# NODE_2_SCH.net
KiCad netlist of a schematic drawn in Altium Designer
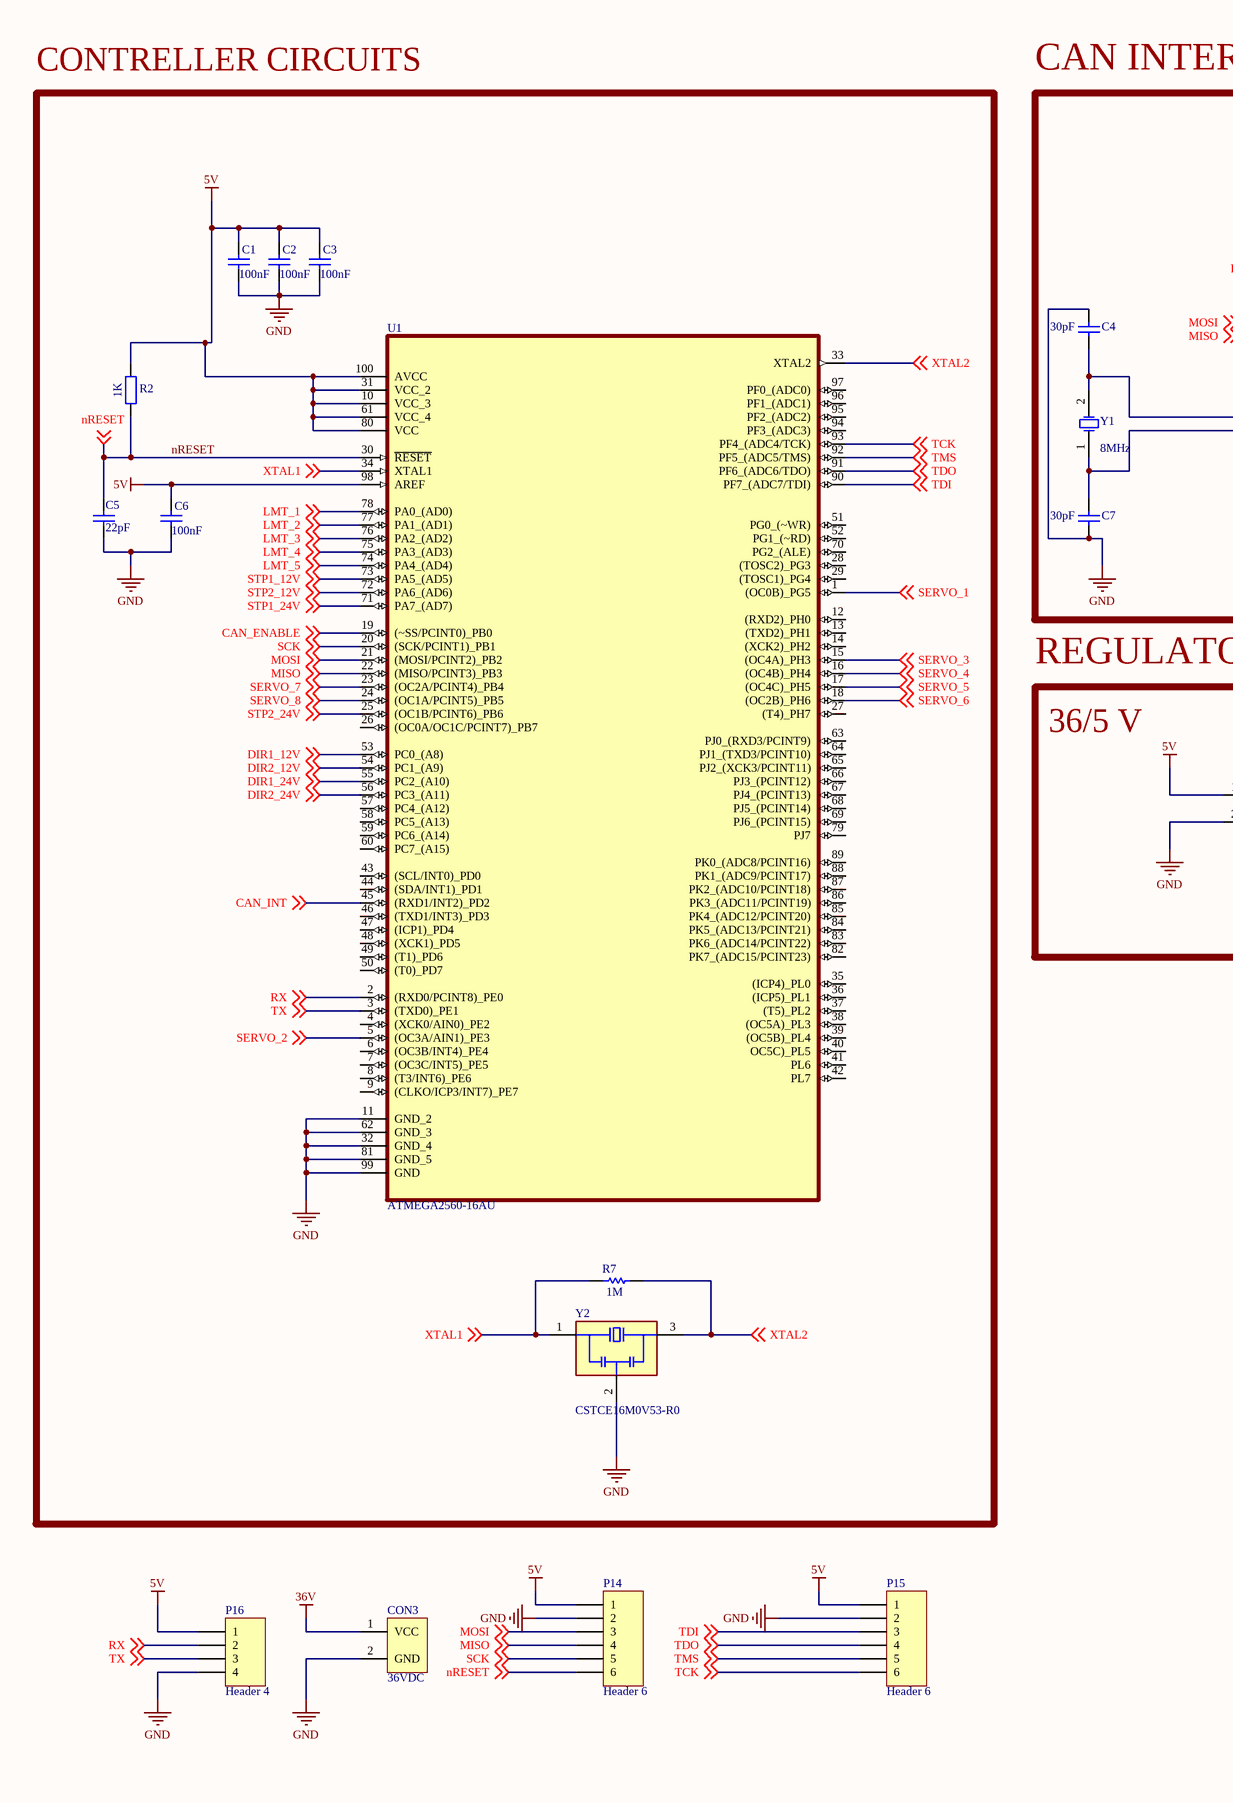
[diagram p0: NODE_2_SCH.SchDoc, left]
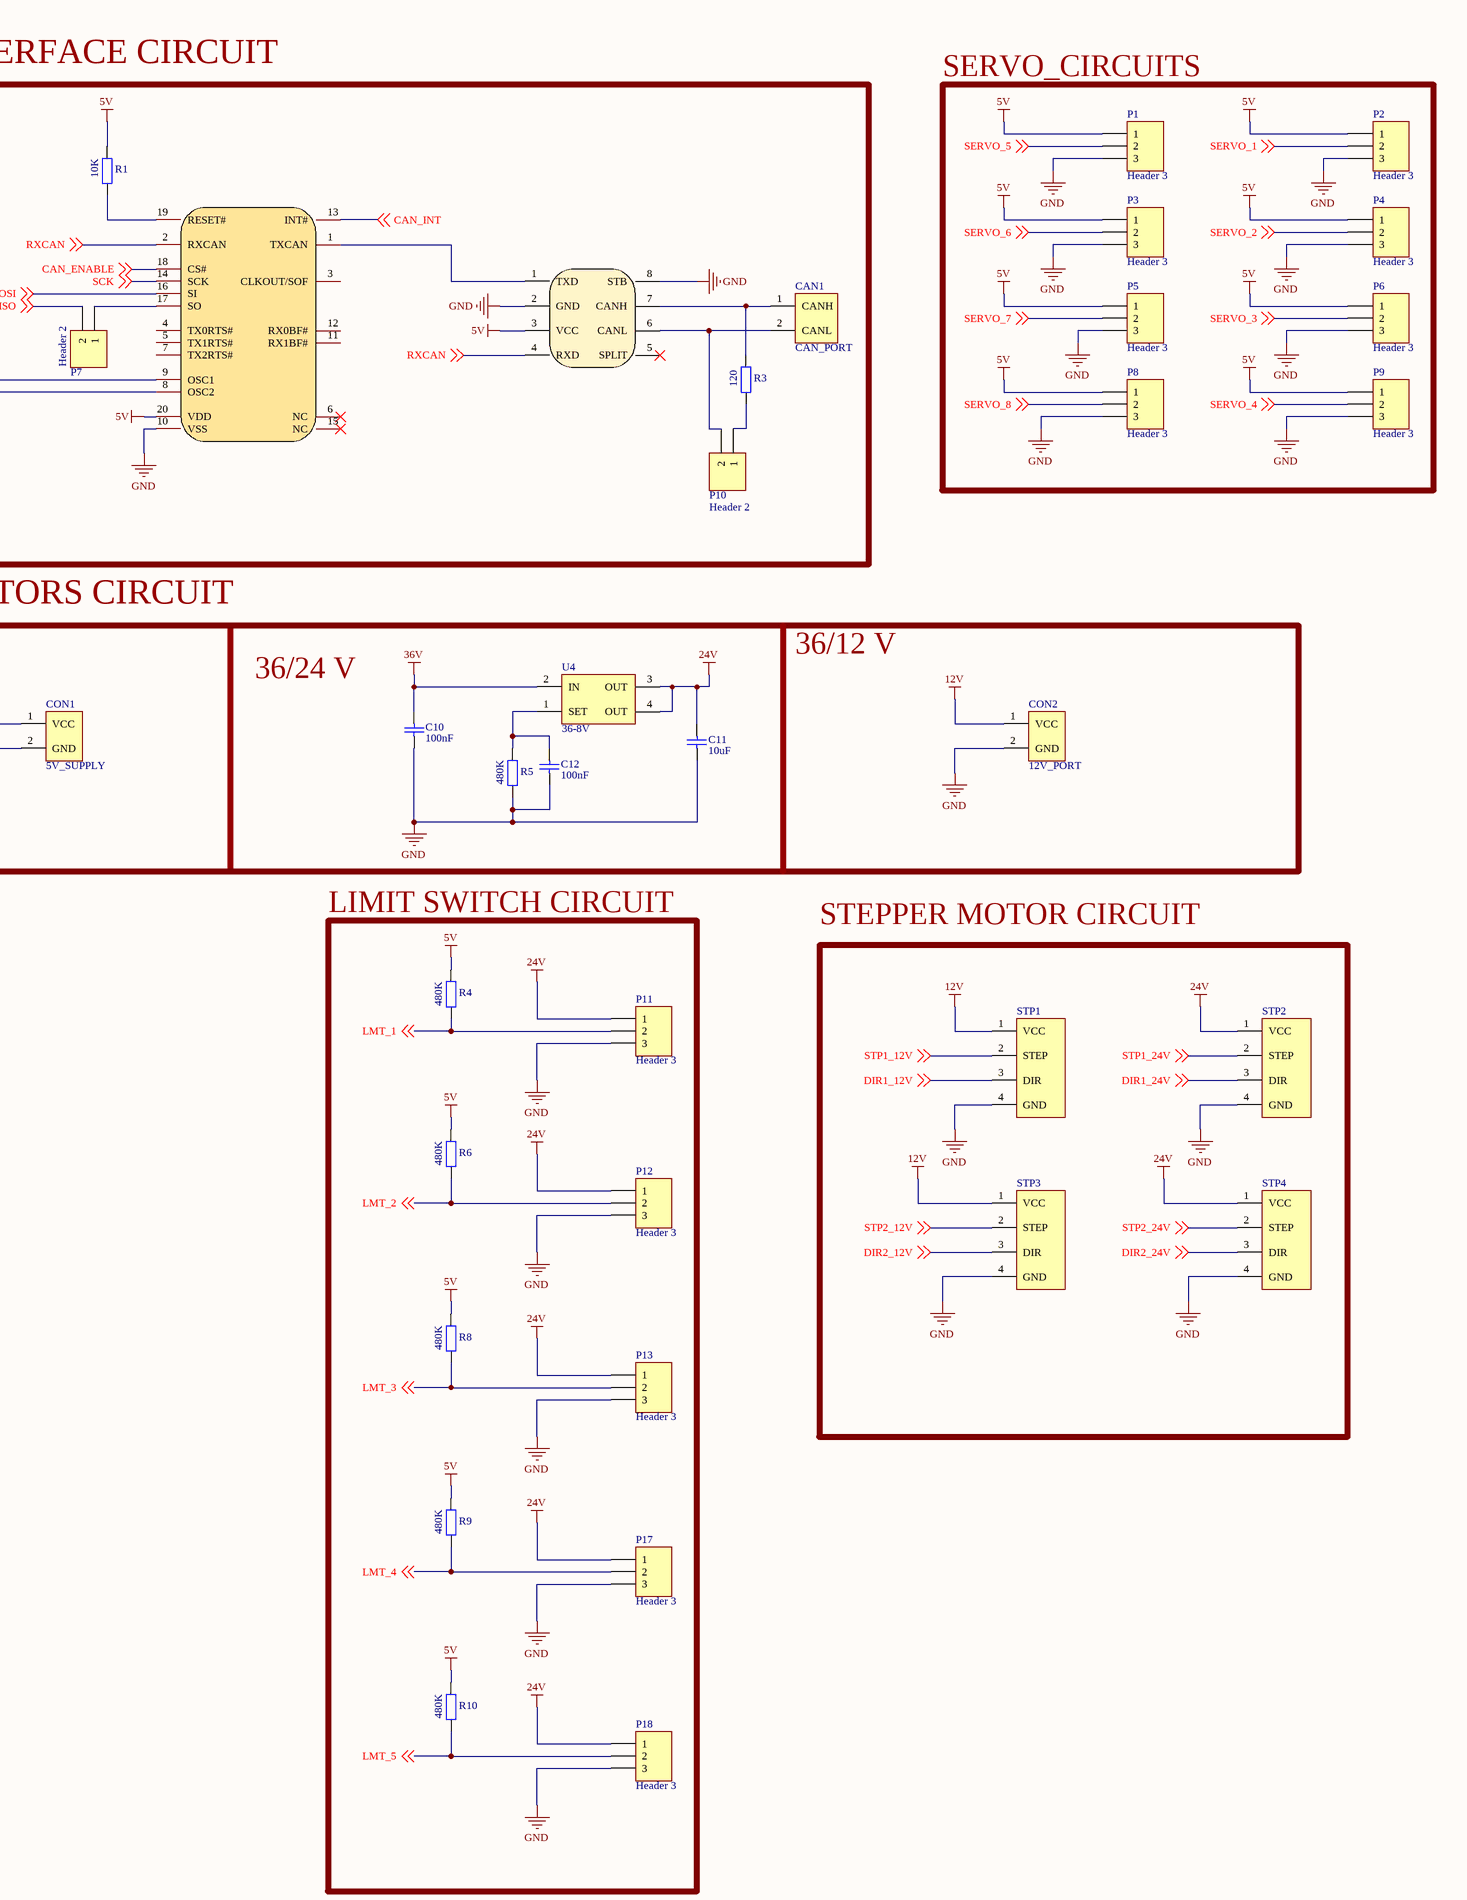
[diagram p1: NODE_2_SCH.SchDoc, right]

(export (version "E")
  (design (tool "Eeschema 10.0.6"))
  (components
    (comp (ref "C1")
      (value "100nF")
      (footprint "CAPC2012X135N")
      (description "Capacitor")
      (fields
        (field (name "PART NUMBER") "TCC0805X7R104M500DT")
        (field (name "Comment") "Cap")
        (field (name "PUBLISHER") "Altium Limited")
      )
      (libsource (lib "Miscellaneous Devices") (part "Cap"))
    )
    (comp (ref "C2")
      (value "100nF")
      (footprint "CAPC2012X135N")
      (description "Capacitor")
      (fields
        (field (name "PART NUMBER") "TCC0805X7R104M500DT")
        (field (name "Comment") "Cap")
        (field (name "PUBLISHER") "Altium Limited")
      )
      (libsource (lib "Miscellaneous Devices") (part "Cap"))
    )
    (comp (ref "C3")
      (value "100nF")
      (footprint "CAPC2012X135N")
      (description "Capacitor")
      (fields
        (field (name "PART NUMBER") "TCC0805X7R104M500DT")
        (field (name "Comment") "Cap")
        (field (name "PUBLISHER") "Altium Limited")
      )
      (libsource (lib "Miscellaneous Devices") (part "Cap"))
    )
    (comp (ref "C4")
      (value "30pF")
      (footprint "CAPC2012X135N")
      (description "Capacitor")
      (fields
        (field (name "PART NUMBER") "TCC0805COG300J500BT")
        (field (name "Comment") "Cap")
        (field (name "PUBLISHER") "Altium Limited")
      )
      (libsource (lib "Miscellaneous Devices") (part "Cap"))
    )
    (comp (ref "C5")
      (value "22pF")
      (footprint "CAPC2012X135N")
      (description "Capacitor")
      (fields
        (field (name "PART NUMBER") "TCC0805COG220J500BT")
        (field (name "Comment") "Cap")
        (field (name "PUBLISHER") "Altium Limited")
      )
      (libsource (lib "Miscellaneous Devices") (part "Cap"))
    )
    (comp (ref "C6")
      (value "100nF")
      (footprint "CAPC2012X135N")
      (description "Capacitor")
      (fields
        (field (name "PART NUMBER") "TCC0805X7R104M500DT")
        (field (name "Comment") "Cap")
        (field (name "PUBLISHER") "Altium Limited")
      )
      (libsource (lib "Miscellaneous Devices") (part "Cap"))
    )
    (comp (ref "C7")
      (value "30pF")
      (footprint "CAPC2012X135N")
      (description "Capacitor")
      (fields
        (field (name "PART NUMBER") "TCC0805COG300J500BT")
        (field (name "Comment") "Cap")
        (field (name "PUBLISHER") "Altium Limited")
      )
      (libsource (lib "Miscellaneous Devices") (part "Cap"))
    )
    (comp (ref "C10")
      (value "100nF")
      (footprint "CAPC2012X135N")
      (description "Capacitor")
      (fields
        (field (name "PART NUMBER") "TCC0805X7R104M500DT")
        (field (name "Comment") "Cap")
        (field (name "PUBLISHER") "Altium Limited")
      )
      (libsource (lib "Miscellaneous Devices") (part "Cap"))
    )
    (comp (ref "C11")
      (value "10uF")
      (footprint "CAPC2012X135N")
      (description "Capacitor")
      (fields
        (field (name "PART NUMBER") "CL21A106KOQNNNE")
        (field (name "Comment") "Cap")
        (field (name "PUBLISHER") "Altium Limited")
      )
      (libsource (lib "Miscellaneous Devices") (part "Cap"))
    )
    (comp (ref "C12")
      (value "100nF")
      (footprint "CAPC2012X135N")
      (description "Capacitor")
      (fields
        (field (name "PART NUMBER") "TCC0805X7R104M500DT")
        (field (name "Comment") "Cap")
        (field (name "PUBLISHER") "Altium Limited")
      )
      (libsource (lib "Miscellaneous Devices") (part "Cap"))
    )
    (comp (ref "CAN1")
      (value "CAN_PORT")
      (footprint "12V_CON")
      (fields (field (name "PART NUMBER") "MX126-5.0-02P-GN01-Cu-S-A"))
      (libsource (lib "IOT_Library") (part "2PIN_CON_1"))
    )
    (comp (ref "CON1")
      (value "5V_SUPPLY")
      (footprint "12V_CON")
      (fields (field (name "PART NUMBER") "MX126-5.0-02P-GN01-Cu-S-A"))
      (libsource (lib "IOT_Library") (part "2PIN_CON"))
    )
    (comp (ref "CON2")
      (value "12V_PORT")
      (footprint "12V_CON")
      (fields (field (name "PART NUMBER") "MX126-5.0-02P-GN01-Cu-S-A"))
      (libsource (lib "IOT_Library") (part "2PIN_CON"))
    )
    (comp (ref "CON3")
      (value "36VDC")
      (footprint "12V_CON")
      (fields (field (name "PART NUMBER") "MX126-5.0-02P-GN01-Cu-S-A"))
      (libsource (lib "IOT_Library") (part "2PIN_CON_2"))
    )
    (comp (ref "P1")
      (value "Header 3")
      (footprint "3PIN_H")
      (description "Header, 3-Pin")
      (fields (field (name "PART NUMBER") "DB125-3.81-3P-BK-S") (field (name "PUBLISHER") "Altium Limited"))
      (libsource (lib "Miscellaneous Connectors") (part "Header 3"))
    )
    (comp (ref "P2")
      (value "Header 3")
      (footprint "3PIN_H")
      (description "Header, 3-Pin")
      (fields (field (name "PART NUMBER") "DB125-3.81-3P-BK-S") (field (name "PUBLISHER") "Altium Limited"))
      (libsource (lib "Miscellaneous Connectors") (part "Header 3"))
    )
    (comp (ref "P3")
      (value "Header 3")
      (footprint "3PIN_H")
      (description "Header, 3-Pin")
      (fields (field (name "PART NUMBER") "DB125-3.81-3P-BK-S") (field (name "PUBLISHER") "Altium Limited"))
      (libsource (lib "Miscellaneous Connectors") (part "Header 3"))
    )
    (comp (ref "P4")
      (value "Header 3")
      (footprint "3PIN_H")
      (description "Header, 3-Pin")
      (fields (field (name "PART NUMBER") "DB125-3.81-3P-BK-S") (field (name "PUBLISHER") "Altium Limited"))
      (libsource (lib "Miscellaneous Connectors") (part "Header 3"))
    )
    (comp (ref "P5")
      (value "Header 3")
      (footprint "3PIN_H")
      (description "Header, 3-Pin")
      (fields (field (name "PART NUMBER") "DB125-3.81-3P-BK-S") (field (name "PUBLISHER") "Altium Limited"))
      (libsource (lib "Miscellaneous Connectors") (part "Header 3"))
    )
    (comp (ref "P6")
      (value "Header 3")
      (footprint "3PIN_H")
      (description "Header, 3-Pin")
      (fields (field (name "PART NUMBER") "DB125-3.81-3P-BK-S") (field (name "PUBLISHER") "Altium Limited"))
      (libsource (lib "Miscellaneous Connectors") (part "Header 3"))
    )
    (comp (ref "P7")
      (value "Header 2")
      (footprint "SAMTEC_TS-102-G-A")
      (description "Header, 2-Pin")
      (fields (field (name "PART NUMBER") "PH-01078") (field (name "PUBLISHER") "Altium Limited"))
      (libsource (lib "Miscellaneous Connectors") (part "Header 2"))
    )
    (comp (ref "P8")
      (value "Header 3")
      (footprint "3PIN_H")
      (description "Header, 3-Pin")
      (fields (field (name "PART NUMBER") "DB125-3.81-3P-BK-S") (field (name "PUBLISHER") "Altium Limited"))
      (libsource (lib "Miscellaneous Connectors") (part "Header 3"))
    )
    (comp (ref "P9")
      (value "Header 3")
      (footprint "3PIN_H")
      (description "Header, 3-Pin")
      (fields (field (name "PART NUMBER") "DB125-3.81-3P-BK-S") (field (name "PUBLISHER") "Altium Limited"))
      (libsource (lib "Miscellaneous Connectors") (part "Header 3"))
    )
    (comp (ref "P10")
      (value "Header 2")
      (footprint "SAMTEC_TS-102-G-A")
      (description "Header, 2-Pin")
      (fields (field (name "PART NUMBER") "PH-01078") (field (name "PUBLISHER") "Altium Limited"))
      (libsource (lib "Miscellaneous Connectors") (part "Header 2"))
    )
    (comp (ref "P11")
      (value "Header 3")
      (footprint "3PIN_H")
      (description "Header, 3-Pin")
      (fields (field (name "PART NUMBER") "DB125-3.81-3P-BK-S") (field (name "PUBLISHER") "Altium Limited"))
      (libsource (lib "Miscellaneous Connectors") (part "Header 3"))
    )
    (comp (ref "P12")
      (value "Header 3")
      (footprint "3PIN_H")
      (description "Header, 3-Pin")
      (fields (field (name "PART NUMBER") "DB125-3.81-3P-BK-S") (field (name "PUBLISHER") "Altium Limited"))
      (libsource (lib "Miscellaneous Connectors") (part "Header 3"))
    )
    (comp (ref "P13")
      (value "Header 3")
      (footprint "3PIN_H")
      (description "Header, 3-Pin")
      (fields (field (name "PART NUMBER") "DB125-3.81-3P-BK-S") (field (name "PUBLISHER") "Altium Limited"))
      (libsource (lib "Miscellaneous Connectors") (part "Header 3"))
    )
    (comp (ref "P14")
      (value "Header 6")
      (footprint "HDR1X6")
      (description "Header, 6-Pin")
      (fields (field (name "PART NUMBER") "P125-1106A0BS116A1") (field (name "PUBLISHER") "Altium Limited"))
      (libsource (lib "Miscellaneous Connectors") (part "Header 6"))
    )
    (comp (ref "P15")
      (value "Header 6")
      (footprint "HDR1X6")
      (description "Header, 6-Pin")
      (fields (field (name "PART NUMBER") "P125-1106A0BS116A1") (field (name "PUBLISHER") "Altium Limited"))
      (libsource (lib "Miscellaneous Connectors") (part "Header 6"))
    )
    (comp (ref "P16")
      (value "Header 4")
      (footprint "HDR1X4")
      (description "Header, 4-Pin")
      (fields (field (name "PART NUMBER") "HB-PH3-25414PB2GOP") (field (name "PUBLISHER") "Altium Limited"))
      (libsource (lib "Miscellaneous Connectors") (part "Header 4"))
    )
    (comp (ref "P17")
      (value "Header 3")
      (footprint "3PIN_H")
      (description "Header, 3-Pin")
      (fields (field (name "PART NUMBER") "DB125-3.81-3P-BK-S") (field (name "PUBLISHER") "Altium Limited"))
      (libsource (lib "Miscellaneous Connectors") (part "Header 3"))
    )
    (comp (ref "P18")
      (value "Header 3")
      (footprint "3PIN_H")
      (description "Header, 3-Pin")
      (fields (field (name "PART NUMBER") "DB125-3.81-3P-BK-S") (field (name "PUBLISHER") "Altium Limited"))
      (libsource (lib "Miscellaneous Connectors") (part "Header 3"))
    )
    (comp (ref "R1")
      (value "10K")
      (footprint "RESC2013X06N")
      (description "Resistor")
      (fields
        (field (name "PART NUMBER") "RC0805JR-0710KL")
        (field (name "Comment") "Res2")
        (field (name "PUBLISHER") "Altium Limited")
      )
      (libsource (lib "Miscellaneous Devices") (part "Res2"))
    )
    (comp (ref "R2")
      (value "1K")
      (footprint "RESC2013X06N")
      (description "Resistor")
      (fields
        (field (name "PART NUMBER") "RC0805JR-071KL")
        (field (name "Comment") "Res2")
        (field (name "PUBLISHER") "Altium Limited")
      )
      (libsource (lib "Miscellaneous Devices") (part "Res2"))
    )
    (comp (ref "R3")
      (value "120")
      (footprint "CRCW1206120RFKEAHP")
      (description "Resistor")
      (fields
        (field (name "PART NUMBER") "CRCW1206120RFKEAHP")
        (field (name "Comment") "Res2")
        (field (name "PUBLISHER") "Altium Limited")
      )
      (libsource (lib "Miscellaneous Devices") (part "Res2"))
    )
    (comp (ref "R4")
      (value "480K")
      (footprint "CRCW1206120RFKEAHP")
      (description "Resistor")
      (fields
        (field (name "PART NUMBER") "1206W4J0484T5E")
        (field (name "Comment") "Res2")
        (field (name "PUBLISHER") "Altium Limited")
      )
      (libsource (lib "Miscellaneous Devices") (part "Res2"))
    )
    (comp (ref "R5")
      (value "480K")
      (footprint "CRCW1206120RFKEAHP")
      (description "Resistor")
      (fields
        (field (name "PART NUMBER") "1206W4J0484T5E")
        (field (name "Comment") "Res2")
        (field (name "PUBLISHER") "Altium Limited")
      )
      (libsource (lib "Miscellaneous Devices") (part "Res2"))
    )
    (comp (ref "R6")
      (value "480K")
      (footprint "CRCW1206120RFKEAHP")
      (description "Resistor")
      (fields
        (field (name "PART NUMBER") "1206W4J0484T5E")
        (field (name "Comment") "Res2")
        (field (name "PUBLISHER") "Altium Limited")
      )
      (libsource (lib "Miscellaneous Devices") (part "Res2"))
    )
    (comp (ref "R7")
      (value "1M")
      (footprint "RESC2013X06N")
      (description "Resistor")
      (fields
        (field (name "PART NUMBER") "RC0805JR-071KL")
        (field (name "Comment") "Res1")
        (field (name "PUBLISHER") "Altium Limited")
      )
      (libsource (lib "Miscellaneous Devices") (part "Res1"))
    )
    (comp (ref "R8")
      (value "480K")
      (footprint "CRCW1206120RFKEAHP")
      (description "Resistor")
      (fields
        (field (name "PART NUMBER") "1206W4J0484T5E")
        (field (name "Comment") "Res2")
        (field (name "PUBLISHER") "Altium Limited")
      )
      (libsource (lib "Miscellaneous Devices") (part "Res2"))
    )
    (comp (ref "R9")
      (value "480K")
      (footprint "CRCW1206120RFKEAHP")
      (description "Resistor")
      (fields
        (field (name "PART NUMBER") "1206W4J0484T5E")
        (field (name "Comment") "Res2")
        (field (name "PUBLISHER") "Altium Limited")
      )
      (libsource (lib "Miscellaneous Devices") (part "Res2"))
    )
    (comp (ref "R10")
      (value "480K")
      (footprint "CRCW1206120RFKEAHP")
      (description "Resistor")
      (fields
        (field (name "PART NUMBER") "1206W4J0484T5E")
        (field (name "Comment") "Res2")
        (field (name "PUBLISHER") "Altium Limited")
      )
      (libsource (lib "Miscellaneous Devices") (part "Res2"))
    )
    (comp (ref "STP1")
      (value "STPR_MTR_PORT")
      (footprint "CONN-TH_4P-P5.08_DIBO_DB128V-5.08 - duplicate1")
      (description "OUTPUT TO SUPPLY THE STEPPER MOTOR NEEDS")
      (fields (field (name "PART NUMBER") "WJ500V-5.08-2P"))
      (libsource (lib "IOT_Library") (part "STPR_MTR_PORT"))
    )
    (comp (ref "STP2")
      (value "STPR_MTR_PORT")
      (footprint "CONN-TH_4P-P5.08_DIBO_DB128V-5.08 - duplicate1")
      (description "OUTPUT TO SUPPLY THE STEPPER MOTOR NEEDS")
      (fields (field (name "PART NUMBER") "WJ500V-5.08-2P"))
      (libsource (lib "IOT_Library") (part "STPR_MTR_PORT"))
    )
    (comp (ref "STP3")
      (value "STPR_MTR_PORT")
      (footprint "CONN-TH_4P-P5.08_DIBO_DB128V-5.08 - duplicate1")
      (description "OUTPUT TO SUPPLY THE STEPPER MOTOR NEEDS")
      (fields (field (name "PART NUMBER") "WJ500V-5.08-2P"))
      (libsource (lib "IOT_Library") (part "STPR_MTR_PORT"))
    )
    (comp (ref "STP4")
      (value "STPR_MTR_PORT")
      (footprint "CONN-TH_4P-P5.08_DIBO_DB128V-5.08 - duplicate1")
      (description "OUTPUT TO SUPPLY THE STEPPER MOTOR NEEDS")
      (fields (field (name "PART NUMBER") "WJ500V-5.08-2P"))
      (libsource (lib "IOT_Library") (part "STPR_MTR_PORT"))
    )
    (comp (ref "U1")
      (value "ATMEGA2560-16AU")
      (footprint "QFP50P1600X1600X120-100N")
      (description "AVR AVRÂ® ATmega Microcontroller IC 8-Bit 16MHz 256KB (128K x 16) FLASH 100-TQFP (14x14)")
      (fields (field (name "MF") "Microchip"))
      (libsource (lib "IOT_Library") (part "ATMEGA2560-16AU"))
    )
    (comp (ref "U2")
      (value "TJA1050DRG")
      (footprint "SOP-8_L4.9-W3.9-P1.27-LS6.0-BL - duplicate")
      (fields (field (name "MANUFACTURER") "HGC(深圳汉芯)"))
      (libsource (lib "IOT_Library") (part "TJA1050DRG"))
    )
    (comp (ref "U3")
      (value "MCP2515T-I/ST")
      (footprint "TSSOP-20_L6.5-W4.4-P0.65-LS6.4-BL")
      (fields (field (name "MANUFACTURER") "MICROCHIP(美国微芯)"))
      (libsource (lib "IOT_Library") (part "MCP2515T-I/ST"))
    )
    (comp (ref "U4")
      (value "36-8V")
      (footprint "SOT-223-3_L6.5-W3.4-P2.30-LS7.0-BR")
      (description "LDO Regulator Pos 0V to 34.5V 0.8A Automotive 4-Pin(3+Tab) SOT-223 Tube")
      (fields
        (field (name "MANUFACTURER") "Analog Devices / Linear Technology")
        (field (name "PART NUMBER") "LT3088MPST#PBF")
      )
      (libsource (lib "IOT_Library") (part "LT3088MPST#PBF"))
    )
    (comp (ref "Y1")
      (value "8MHz")
      (footprint "CRYSTAL-SMD_L7.4-W4.0-LS8.0")
      (description "Crystal Oscillator")
      (fields
        (field (name "PART NUMBER") "S47SMD8.000M12PF20R30B3")
        (field (name "Comment") "XTAL")
        (field (name "PUBLISHER") "Altium Limited")
      )
      (libsource (lib "Miscellaneous Devices") (part "XTAL"))
    )
    (comp (ref "Y2")
      (value "CSTCE16M0V53-R0")
      (footprint "OSC_CSTCE16M0V53-R0")
      (description "16 MHz Ceramic Resonator Built in Capacitor 15 pF Â±0.3% -20Â°C ~ 80Â°C Surface Mount")
      (fields (field (name "MF") "Murata"))
      (libsource (lib "IOT_Library") (part "CSTCE16M0V53-R0"))
    )
  )
  (nets
    (net (code "1") (name "5V") (class "Default")
      (node (ref "C1") (pin "1") (pinfunction "1_1") (pintype "passive"))
      (node (ref "C2") (pin "1") (pinfunction "1_1") (pintype "passive"))
      (node (ref "C3") (pin "1") (pinfunction "1_1") (pintype "passive"))
      (node (ref "C6") (pin "1") (pinfunction "1_1") (pintype "passive"))
      (node (ref "CON1") (pin "1") (pinfunction "VCC_1") (pintype "passive"))
      (node (ref "P1") (pin "1") (pinfunction "1_1") (pintype "passive"))
      (node (ref "P14") (pin "1") (pinfunction "1_1") (pintype "passive"))
      (node (ref "P15") (pin "1") (pinfunction "1_1") (pintype "passive"))
      (node (ref "P16") (pin "1") (pinfunction "1_1") (pintype "passive"))
      (node (ref "P2") (pin "1") (pinfunction "1_1") (pintype "passive"))
      (node (ref "P3") (pin "1") (pinfunction "1_1") (pintype "passive"))
      (node (ref "P4") (pin "1") (pinfunction "1_1") (pintype "passive"))
      (node (ref "P5") (pin "1") (pinfunction "1_1") (pintype "passive"))
      (node (ref "P6") (pin "1") (pinfunction "1_1") (pintype "passive"))
      (node (ref "P8") (pin "1") (pinfunction "1_1") (pintype "passive"))
      (node (ref "P9") (pin "1") (pinfunction "1_1") (pintype "passive"))
      (node (ref "R1") (pin "2") (pinfunction "2_2") (pintype "passive"))
      (node (ref "R10") (pin "2") (pinfunction "2_2") (pintype "passive"))
      (node (ref "R2") (pin "2") (pinfunction "2_2") (pintype "passive"))
      (node (ref "R4") (pin "2") (pinfunction "2_2") (pintype "passive"))
      (node (ref "R6") (pin "2") (pinfunction "2_2") (pintype "passive"))
      (node (ref "R8") (pin "2") (pinfunction "2_2") (pintype "passive"))
      (node (ref "R9") (pin "2") (pinfunction "2_2") (pintype "passive"))
      (node (ref "U1") (pin "10") (pinfunction "VCC_3_10") (pintype "power_in"))
      (node (ref "U1") (pin "100") (pinfunction "AVCC_100") (pintype "power_in"))
      (node (ref "U1") (pin "31") (pinfunction "VCC_2_31") (pintype "power_in"))
      (node (ref "U1") (pin "61") (pinfunction "VCC_4_61") (pintype "power_in"))
      (node (ref "U1") (pin "80") (pinfunction "VCC_80") (pintype "power_in"))
      (node (ref "U1") (pin "98") (pinfunction "AREF_98") (pintype "input"))
      (node (ref "U2") (pin "3") (pinfunction "VCC_3") (pintype "passive"))
      (node (ref "U3") (pin "20") (pinfunction "VDD_20") (pintype "passive"))
    )
    (net (code "2") (name "12V") (class "Default")
      (node (ref "CON2") (pin "1") (pinfunction "VCC_1") (pintype "passive"))
      (node (ref "STP1") (pin "1") (pinfunction "VCC_1") (pintype "passive"))
      (node (ref "STP3") (pin "1") (pinfunction "VCC_1") (pintype "passive"))
    )
    (net (code "3") (name "24V") (class "Default")
      (node (ref "C11") (pin "2") (pinfunction "2_2") (pintype "passive"))
      (node (ref "P11") (pin "1") (pinfunction "1_1") (pintype "passive"))
      (node (ref "P12") (pin "1") (pinfunction "1_1") (pintype "passive"))
      (node (ref "P13") (pin "1") (pinfunction "1_1") (pintype "passive"))
      (node (ref "P17") (pin "1") (pinfunction "1_1") (pintype "passive"))
      (node (ref "P18") (pin "1") (pinfunction "1_1") (pintype "passive"))
      (node (ref "STP2") (pin "1") (pinfunction "VCC_1") (pintype "passive"))
      (node (ref "STP4") (pin "1") (pinfunction "VCC_1") (pintype "passive"))
      (node (ref "U4") (pin "3") (pinfunction "OUT_3") (pintype "passive"))
      (node (ref "U4") (pin "4") (pinfunction "OUT_4") (pintype "passive"))
    )
    (net (code "4") (name "36V") (class "Default")
      (node (ref "C10") (pin "2") (pinfunction "2_2") (pintype "passive"))
      (node (ref "CON3") (pin "1") (pinfunction "VCC_1") (pintype "passive"))
      (node (ref "U4") (pin "2") (pinfunction "IN_2") (pintype "passive"))
    )
    (net (code "5") (name "CAN_ENABLE") (class "Default")
      (node (ref "U1") (pin "19") (pinfunction "(~SS/PCINT0)_PB0_19") (pintype "bidirectional"))
      (node (ref "U3") (pin "18") (pinfunction "CS#_18") (pintype "passive"))
    )
    (net (code "6") (name "CAN_INT") (class "Default")
      (node (ref "U1") (pin "45") (pinfunction "(RXD1/INT2)_PD2_45") (pintype "bidirectional"))
      (node (ref "U3") (pin "13") (pinfunction "INT#_13") (pintype "passive"))
    )
    (net (code "7") (name "DIR1_12V") (class "Default")
      (node (ref "STP1") (pin "3") (pinfunction "DIR_3") (pintype "passive"))
      (node (ref "U1") (pin "53") (pinfunction "PC0_(A8)_53") (pintype "bidirectional"))
    )
    (net (code "8") (name "DIR1_24V") (class "Default")
      (node (ref "STP2") (pin "3") (pinfunction "DIR_3") (pintype "passive"))
      (node (ref "U1") (pin "55") (pinfunction "PC2_(A10)_55") (pintype "bidirectional"))
    )
    (net (code "9") (name "DIR2_12V") (class "Default")
      (node (ref "STP3") (pin "3") (pinfunction "DIR_3") (pintype "passive"))
      (node (ref "U1") (pin "54") (pinfunction "PC1_(A9)_54") (pintype "bidirectional"))
    )
    (net (code "10") (name "DIR2_24V") (class "Default")
      (node (ref "STP4") (pin "3") (pinfunction "DIR_3") (pintype "passive"))
      (node (ref "U1") (pin "56") (pinfunction "PC3_(A11)_56") (pintype "bidirectional"))
    )
    (net (code "11") (name "GND") (class "Default")
      (node (ref "C1") (pin "2") (pinfunction "2_2") (pintype "passive"))
      (node (ref "C10") (pin "1") (pinfunction "1_1") (pintype "passive"))
      (node (ref "C11") (pin "1") (pinfunction "1_1") (pintype "passive"))
      (node (ref "C12") (pin "1") (pinfunction "1_1") (pintype "passive"))
      (node (ref "C2") (pin "2") (pinfunction "2_2") (pintype "passive"))
      (node (ref "C3") (pin "2") (pinfunction "2_2") (pintype "passive"))
      (node (ref "C4") (pin "1") (pinfunction "1_1") (pintype "passive"))
      (node (ref "C5") (pin "2") (pinfunction "2_2") (pintype "passive"))
      (node (ref "C6") (pin "2") (pinfunction "2_2") (pintype "passive"))
      (node (ref "C7") (pin "2") (pinfunction "2_2") (pintype "passive"))
      (node (ref "CON1") (pin "2") (pinfunction "GND_2") (pintype "passive"))
      (node (ref "CON2") (pin "2") (pinfunction "GND_2") (pintype "passive"))
      (node (ref "CON3") (pin "2") (pinfunction "GND_2") (pintype "passive"))
      (node (ref "P1") (pin "3") (pinfunction "3_3") (pintype "passive"))
      (node (ref "P11") (pin "3") (pinfunction "3_3") (pintype "passive"))
      (node (ref "P12") (pin "3") (pinfunction "3_3") (pintype "passive"))
      (node (ref "P13") (pin "3") (pinfunction "3_3") (pintype "passive"))
      (node (ref "P14") (pin "2") (pinfunction "2_2") (pintype "passive"))
      (node (ref "P15") (pin "2") (pinfunction "2_2") (pintype "passive"))
      (node (ref "P16") (pin "4") (pinfunction "4_4") (pintype "passive"))
      (node (ref "P17") (pin "3") (pinfunction "3_3") (pintype "passive"))
      (node (ref "P18") (pin "3") (pinfunction "3_3") (pintype "passive"))
      (node (ref "P2") (pin "3") (pinfunction "3_3") (pintype "passive"))
      (node (ref "P3") (pin "3") (pinfunction "3_3") (pintype "passive"))
      (node (ref "P4") (pin "3") (pinfunction "3_3") (pintype "passive"))
      (node (ref "P5") (pin "3") (pinfunction "3_3") (pintype "passive"))
      (node (ref "P6") (pin "3") (pinfunction "3_3") (pintype "passive"))
      (node (ref "P8") (pin "3") (pinfunction "3_3") (pintype "passive"))
      (node (ref "P9") (pin "3") (pinfunction "3_3") (pintype "passive"))
      (node (ref "R5") (pin "1") (pinfunction "1_1") (pintype "passive"))
      (node (ref "STP1") (pin "4") (pinfunction "GND_4") (pintype "passive"))
      (node (ref "STP2") (pin "4") (pinfunction "GND_4") (pintype "passive"))
      (node (ref "STP3") (pin "4") (pinfunction "GND_4") (pintype "passive"))
      (node (ref "STP4") (pin "4") (pinfunction "GND_4") (pintype "passive"))
      (node (ref "U1") (pin "11") (pinfunction "GND_2_11") (pintype "passive"))
      (node (ref "U1") (pin "32") (pinfunction "GND_4_32") (pintype "passive"))
      (node (ref "U1") (pin "62") (pinfunction "GND_3_62") (pintype "passive"))
      (node (ref "U1") (pin "81") (pinfunction "GND_5_81") (pintype "passive"))
      (node (ref "U1") (pin "99") (pinfunction "GND_99") (pintype "passive"))
      (node (ref "U2") (pin "2") (pinfunction "GND_2") (pintype "passive"))
      (node (ref "U2") (pin "8") (pinfunction "STB_8") (pintype "passive"))
      (node (ref "U3") (pin "10") (pinfunction "VSS_10") (pintype "passive"))
      (node (ref "Y2") (pin "2") (pinfunction "GND_2") (pintype "power_in"))
    )
    (net (code "12") (name "LMT_1") (class "Default")
      (node (ref "P11") (pin "2") (pinfunction "2_2") (pintype "passive"))
      (node (ref "R4") (pin "1") (pinfunction "1_1") (pintype "passive"))
      (node (ref "U1") (pin "78") (pinfunction "PA0_(AD0)_78") (pintype "bidirectional"))
    )
    (net (code "13") (name "LMT_2") (class "Default")
      (node (ref "P12") (pin "2") (pinfunction "2_2") (pintype "passive"))
      (node (ref "R6") (pin "1") (pinfunction "1_1") (pintype "passive"))
      (node (ref "U1") (pin "77") (pinfunction "PA1_(AD1)_77") (pintype "bidirectional"))
    )
    (net (code "14") (name "LMT_3") (class "Default")
      (node (ref "P13") (pin "2") (pinfunction "2_2") (pintype "passive"))
      (node (ref "R8") (pin "1") (pinfunction "1_1") (pintype "passive"))
      (node (ref "U1") (pin "76") (pinfunction "PA2_(AD2)_76") (pintype "bidirectional"))
    )
    (net (code "15") (name "LMT_4") (class "Default")
      (node (ref "P17") (pin "2") (pinfunction "2_2") (pintype "passive"))
      (node (ref "R9") (pin "1") (pinfunction "1_1") (pintype "passive"))
      (node (ref "U1") (pin "75") (pinfunction "PA3_(AD3)_75") (pintype "bidirectional"))
    )
    (net (code "16") (name "LMT_5") (class "Default")
      (node (ref "P18") (pin "2") (pinfunction "2_2") (pintype "passive"))
      (node (ref "R10") (pin "1") (pinfunction "1_1") (pintype "passive"))
      (node (ref "U1") (pin "74") (pinfunction "PA4_(AD4)_74") (pintype "bidirectional"))
    )
    (net (code "17") (name "MISO") (class "Default")
      (node (ref "P14") (pin "4") (pinfunction "4_4") (pintype "passive"))
      (node (ref "P7") (pin "2") (pinfunction "2_2") (pintype "passive"))
      (node (ref "U1") (pin "22") (pinfunction "(MISO/PCINT3)_PB3_22") (pintype "bidirectional"))
    )
    (net (code "18") (name "MOSI") (class "Default")
      (node (ref "P14") (pin "3") (pinfunction "3_3") (pintype "passive"))
      (node (ref "U1") (pin "21") (pinfunction "(MOSI/PCINT2)_PB2_21") (pintype "bidirectional"))
      (node (ref "U3") (pin "16") (pinfunction "SI_16") (pintype "passive"))
    )
    (net (code "19") (name "Net-(CAN1-CANH)") (class "Default")
      (node (ref "CAN1") (pin "1") (pinfunction "CANH_1") (pintype "passive"))
      (node (ref "R3") (pin "2") (pinfunction "2_2") (pintype "passive"))
      (node (ref "U2") (pin "7") (pinfunction "CANH_7") (pintype "passive"))
    )
    (net (code "20") (name "Net-(CAN1-CANL)") (class "Default")
      (node (ref "CAN1") (pin "2") (pinfunction "CANL_2") (pintype "passive"))
      (node (ref "P10") (pin "2") (pinfunction "2_2") (pintype "passive"))
      (node (ref "U2") (pin "6") (pinfunction "CANL_6") (pintype "passive"))
    )
    (net (code "21") (name "Net-(P10-Pad1)") (class "Default")
      (node (ref "P10") (pin "1") (pinfunction "1_1") (pintype "passive"))
      (node (ref "R3") (pin "1") (pinfunction "1_1") (pintype "passive"))
    )
    (net (code "22") (name "Net-(U2-TXD)") (class "Default")
      (node (ref "U2") (pin "1") (pinfunction "TXD_1") (pintype "passive"))
      (node (ref "U3") (pin "1") (pinfunction "TXCAN_1") (pintype "passive"))
    )
    (net (code "23") (name "Net-(U3-OSC1)") (class "Default")
      (node (ref "C4") (pin "2") (pinfunction "2_2") (pintype "passive"))
      (node (ref "U3") (pin "9") (pinfunction "OSC1_9") (pintype "passive"))
      (node (ref "Y1") (pin "2") (pinfunction "OSC2_2") (pintype "passive"))
    )
    (net (code "24") (name "Net-(U3-OSC2)") (class "Default")
      (node (ref "C7") (pin "1") (pinfunction "1_1") (pintype "passive"))
      (node (ref "U3") (pin "8") (pinfunction "OSC2_8") (pintype "passive"))
      (node (ref "Y1") (pin "1") (pinfunction "OSC1_1") (pintype "passive"))
    )
    (net (code "25") (name "Net-(U3-RESET#)") (class "Default")
      (node (ref "R1") (pin "1") (pinfunction "1_1") (pintype "passive"))
      (node (ref "U3") (pin "19") (pinfunction "RESET#_19") (pintype "passive"))
    )
    (net (code "26") (name "Net-(U3-SO)") (class "Default")
      (node (ref "P7") (pin "1") (pinfunction "1_1") (pintype "passive"))
      (node (ref "U3") (pin "17") (pinfunction "SO_17") (pintype "passive"))
    )
    (net (code "27") (name "Net-(U4-SET)") (class "Default")
      (node (ref "C12") (pin "2") (pinfunction "2_2") (pintype "passive"))
      (node (ref "R5") (pin "2") (pinfunction "2_2") (pintype "passive"))
      (node (ref "U4") (pin "1") (pinfunction "SET_1") (pintype "passive"))
    )
    (net (code "28") (name "RX") (class "Default")
      (node (ref "P16") (pin "2") (pinfunction "2_2") (pintype "passive"))
      (node (ref "U1") (pin "2") (pinfunction "(RXD0/PCINT8)_PE0_2") (pintype "bidirectional"))
    )
    (net (code "29") (name "RXCAN") (class "Default")
      (node (ref "U2") (pin "4") (pinfunction "RXD_4") (pintype "passive"))
      (node (ref "U3") (pin "2") (pinfunction "RXCAN_2") (pintype "passive"))
    )
    (net (code "30") (name "SCK") (class "Default")
      (node (ref "P14") (pin "5") (pinfunction "5_5") (pintype "passive"))
      (node (ref "U1") (pin "20") (pinfunction "(SCK/PCINT1)_PB1_20") (pintype "bidirectional"))
      (node (ref "U3") (pin "14") (pinfunction "SCK_14") (pintype "passive"))
    )
    (net (code "31") (name "SERVO_1") (class "Default")
      (node (ref "P2") (pin "2") (pinfunction "2_2") (pintype "passive"))
      (node (ref "U1") (pin "1") (pinfunction "(OC0B)_PG5_1") (pintype "bidirectional"))
    )
    (net (code "32") (name "SERVO_2") (class "Default")
      (node (ref "P4") (pin "2") (pinfunction "2_2") (pintype "passive"))
      (node (ref "U1") (pin "5") (pinfunction "(OC3A/AIN1)_PE3_5") (pintype "bidirectional"))
    )
    (net (code "33") (name "SERVO_3") (class "Default")
      (node (ref "P6") (pin "2") (pinfunction "2_2") (pintype "passive"))
      (node (ref "U1") (pin "15") (pinfunction "(OC4A)_PH3_15") (pintype "bidirectional"))
    )
    (net (code "34") (name "SERVO_4") (class "Default")
      (node (ref "P9") (pin "2") (pinfunction "2_2") (pintype "passive"))
      (node (ref "U1") (pin "16") (pinfunction "(OC4B)_PH4_16") (pintype "bidirectional"))
    )
    (net (code "35") (name "SERVO_5") (class "Default")
      (node (ref "P1") (pin "2") (pinfunction "2_2") (pintype "passive"))
      (node (ref "U1") (pin "17") (pinfunction "(OC4C)_PH5_17") (pintype "bidirectional"))
    )
    (net (code "36") (name "SERVO_6") (class "Default")
      (node (ref "P3") (pin "2") (pinfunction "2_2") (pintype "passive"))
      (node (ref "U1") (pin "18") (pinfunction "(OC2B)_PH6_18") (pintype "bidirectional"))
    )
    (net (code "37") (name "SERVO_7") (class "Default")
      (node (ref "P5") (pin "2") (pinfunction "2_2") (pintype "passive"))
      (node (ref "U1") (pin "23") (pinfunction "(OC2A/PCINT4)_PB4_23") (pintype "bidirectional"))
    )
    (net (code "38") (name "SERVO_8") (class "Default")
      (node (ref "P8") (pin "2") (pinfunction "2_2") (pintype "passive"))
      (node (ref "U1") (pin "24") (pinfunction "(OC1A/PCINT5)_PB5_24") (pintype "bidirectional"))
    )
    (net (code "39") (name "STP1_12V") (class "Default")
      (node (ref "STP1") (pin "2") (pinfunction "STEP_2") (pintype "passive"))
      (node (ref "U1") (pin "73") (pinfunction "PA5_(AD5)_73") (pintype "bidirectional"))
    )
    (net (code "40") (name "STP1_24V") (class "Default")
      (node (ref "STP2") (pin "2") (pinfunction "STEP_2") (pintype "passive"))
      (node (ref "U1") (pin "71") (pinfunction "PA7_(AD7)_71") (pintype "bidirectional"))
    )
    (net (code "41") (name "STP2_12V") (class "Default")
      (node (ref "STP3") (pin "2") (pinfunction "STEP_2") (pintype "passive"))
      (node (ref "U1") (pin "72") (pinfunction "PA6_(AD6)_72") (pintype "bidirectional"))
    )
    (net (code "42") (name "STP2_24V") (class "Default")
      (node (ref "STP4") (pin "2") (pinfunction "STEP_2") (pintype "passive"))
      (node (ref "U1") (pin "25") (pinfunction "(OC1B/PCINT6)_PB6_25") (pintype "bidirectional"))
    )
    (net (code "43") (name "TCK") (class "Default")
      (node (ref "P15") (pin "6") (pinfunction "6_6") (pintype "passive"))
      (node (ref "U1") (pin "93") (pinfunction "PF4_(ADC4/TCK)_93") (pintype "bidirectional"))
    )
    (net (code "44") (name "TDI") (class "Default")
      (node (ref "P15") (pin "3") (pinfunction "3_3") (pintype "passive"))
      (node (ref "U1") (pin "90") (pinfunction "PF7_(ADC7/TDI)_90") (pintype "bidirectional"))
    )
    (net (code "45") (name "TDO") (class "Default")
      (node (ref "P15") (pin "4") (pinfunction "4_4") (pintype "passive"))
      (node (ref "U1") (pin "91") (pinfunction "PF6_(ADC6/TDO)_91") (pintype "bidirectional"))
    )
    (net (code "46") (name "TMS") (class "Default")
      (node (ref "P15") (pin "5") (pinfunction "5_5") (pintype "passive"))
      (node (ref "U1") (pin "92") (pinfunction "PF5_(ADC5/TMS)_92") (pintype "bidirectional"))
    )
    (net (code "47") (name "TX") (class "Default")
      (node (ref "P16") (pin "3") (pinfunction "3_3") (pintype "passive"))
      (node (ref "U1") (pin "3") (pinfunction "(TXD0)_PE1_3") (pintype "bidirectional"))
    )
    (net (code "48") (name "XTAL1") (class "Default")
      (node (ref "R7") (pin "1") (pinfunction "1_1") (pintype "passive"))
      (node (ref "U1") (pin "34") (pinfunction "XTAL1_34") (pintype "input"))
      (node (ref "Y2") (pin "1") (pinfunction "IN_1") (pintype "passive"))
    )
    (net (code "49") (name "XTAL2") (class "Default")
      (node (ref "R7") (pin "2") (pinfunction "2_2") (pintype "passive"))
      (node (ref "U1") (pin "33") (pinfunction "XTAL2_33") (pintype "output"))
      (node (ref "Y2") (pin "3") (pinfunction "OUT_3") (pintype "passive"))
    )
    (net (code "50") (name "nRESET") (class "Default")
      (node (ref "C5") (pin "1") (pinfunction "1_1") (pintype "passive"))
      (node (ref "P14") (pin "6") (pinfunction "6_6") (pintype "passive"))
      (node (ref "R2") (pin "1") (pinfunction "1_1") (pintype "passive"))
      (node (ref "U1") (pin "30") (pinfunction "~{RESET}_30") (pintype "input"))
    )
    (net (code "51") (name "unconnected-(U1-(CLKO{slash}ICP3{slash}INT7)_PE7-Pad9)") (class "Default")
      (node (ref "U1") (pin "9") (pinfunction "(CLKO/ICP3/INT7)_PE7_9") (pintype "bidirectional"))
    )
    (net (code "52") (name "unconnected-(U1-(ICP1)_PD4-Pad47)") (class "Default")
      (node (ref "U1") (pin "47") (pinfunction "(ICP1)_PD4_47") (pintype "bidirectional"))
    )
    (net (code "53") (name "unconnected-(U1-(ICP4)_PL0-Pad35)") (class "Default")
      (node (ref "U1") (pin "35") (pinfunction "(ICP4)_PL0_35") (pintype "bidirectional"))
    )
    (net (code "54") (name "unconnected-(U1-(ICP5)_PL1-Pad36)") (class "Default")
      (node (ref "U1") (pin "36") (pinfunction "(ICP5)_PL1_36") (pintype "bidirectional"))
    )
    (net (code "55") (name "unconnected-(U1-(OC0A{slash}OC1C{slash}PCINT7)_PB7-Pad26)") (class "Default")
      (node (ref "U1") (pin "26") (pinfunction "(OC0A/OC1C/PCINT7)_PB7_26") (pintype "bidirectional"))
    )
    (net (code "56") (name "unconnected-(U1-(OC3B{slash}INT4)_PE4-Pad6)") (class "Default")
      (node (ref "U1") (pin "6") (pinfunction "(OC3B/INT4)_PE4_6") (pintype "bidirectional"))
    )
    (net (code "57") (name "unconnected-(U1-(OC3C{slash}INT5)_PE5-Pad7)") (class "Default")
      (node (ref "U1") (pin "7") (pinfunction "(OC3C/INT5)_PE5_7") (pintype "bidirectional"))
    )
    (net (code "58") (name "unconnected-(U1-(OC5A)_PL3-Pad38)") (class "Default")
      (node (ref "U1") (pin "38") (pinfunction "(OC5A)_PL3_38") (pintype "bidirectional"))
    )
    (net (code "59") (name "unconnected-(U1-(OC5B)_PL4-Pad39)") (class "Default")
      (node (ref "U1") (pin "39") (pinfunction "(OC5B)_PL4_39") (pintype "bidirectional"))
    )
    (net (code "60") (name "unconnected-(U1-(RXD2)_PH0-Pad12)") (class "Default")
      (node (ref "U1") (pin "12") (pinfunction "(RXD2)_PH0_12") (pintype "bidirectional"))
    )
    (net (code "61") (name "unconnected-(U1-(SCL{slash}INT0)_PD0-Pad43)") (class "Default")
      (node (ref "U1") (pin "43") (pinfunction "(SCL/INT0)_PD0_43") (pintype "bidirectional"))
    )
    (net (code "62") (name "unconnected-(U1-(SDA{slash}INT1)_PD1-Pad44)") (class "Default")
      (node (ref "U1") (pin "44") (pinfunction "(SDA/INT1)_PD1_44") (pintype "bidirectional"))
    )
    (net (code "63") (name "unconnected-(U1-(T0)_PD7-Pad50)") (class "Default")
      (node (ref "U1") (pin "50") (pinfunction "(T0)_PD7_50") (pintype "bidirectional"))
    )
    (net (code "64") (name "unconnected-(U1-(T1)_PD6-Pad49)") (class "Default")
      (node (ref "U1") (pin "49") (pinfunction "(T1)_PD6_49") (pintype "bidirectional"))
    )
    (net (code "65") (name "unconnected-(U1-(T3{slash}INT6)_PE6-Pad8)") (class "Default")
      (node (ref "U1") (pin "8") (pinfunction "(T3/INT6)_PE6_8") (pintype "bidirectional"))
    )
    (net (code "66") (name "unconnected-(U1-(T4)_PH7-Pad27)") (class "Default")
      (node (ref "U1") (pin "27") (pinfunction "(T4)_PH7_27") (pintype "bidirectional"))
    )
    (net (code "67") (name "unconnected-(U1-(T5)_PL2-Pad37)") (class "Default")
      (node (ref "U1") (pin "37") (pinfunction "(T5)_PL2_37") (pintype "bidirectional"))
    )
    (net (code "68") (name "unconnected-(U1-(TOSC1)_PG4-Pad29)") (class "Default")
      (node (ref "U1") (pin "29") (pinfunction "(TOSC1)_PG4_29") (pintype "bidirectional"))
    )
    (net (code "69") (name "unconnected-(U1-(TOSC2)_PG3-Pad28)") (class "Default")
      (node (ref "U1") (pin "28") (pinfunction "(TOSC2)_PG3_28") (pintype "bidirectional"))
    )
    (net (code "70") (name "unconnected-(U1-(TXD1{slash}INT3)_PD3-Pad46)") (class "Default")
      (node (ref "U1") (pin "46") (pinfunction "(TXD1/INT3)_PD3_46") (pintype "bidirectional"))
    )
    (net (code "71") (name "unconnected-(U1-(TXD2)_PH1-Pad13)") (class "Default")
      (node (ref "U1") (pin "13") (pinfunction "(TXD2)_PH1_13") (pintype "bidirectional"))
    )
    (net (code "72") (name "unconnected-(U1-(XCK0{slash}AIN0)_PE2-Pad4)") (class "Default")
      (node (ref "U1") (pin "4") (pinfunction "(XCK0/AIN0)_PE2_4") (pintype "bidirectional"))
    )
    (net (code "73") (name "unconnected-(U1-(XCK1)_PD5-Pad48)") (class "Default")
      (node (ref "U1") (pin "48") (pinfunction "(XCK1)_PD5_48") (pintype "bidirectional"))
    )
    (net (code "74") (name "unconnected-(U1-(XCK2)_PH2-Pad14)") (class "Default")
      (node (ref "U1") (pin "14") (pinfunction "(XCK2)_PH2_14") (pintype "bidirectional"))
    )
    (net (code "75") (name "unconnected-(U1-OC5C)_PL5-Pad40)") (class "Default")
      (node (ref "U1") (pin "40") (pinfunction "OC5C)_PL5_40") (pintype "bidirectional"))
    )
    (net (code "76") (name "unconnected-(U1-PC4_(A12)-Pad57)") (class "Default")
      (node (ref "U1") (pin "57") (pinfunction "PC4_(A12)_57") (pintype "bidirectional"))
    )
    (net (code "77") (name "unconnected-(U1-PC5_(A13)-Pad58)") (class "Default")
      (node (ref "U1") (pin "58") (pinfunction "PC5_(A13)_58") (pintype "bidirectional"))
    )
    (net (code "78") (name "unconnected-(U1-PC6_(A14)-Pad59)") (class "Default")
      (node (ref "U1") (pin "59") (pinfunction "PC6_(A14)_59") (pintype "bidirectional"))
    )
    (net (code "79") (name "unconnected-(U1-PC7_(A15)-Pad60)") (class "Default")
      (node (ref "U1") (pin "60") (pinfunction "PC7_(A15)_60") (pintype "bidirectional"))
    )
    (net (code "80") (name "unconnected-(U1-PF0_(ADC0)-Pad97)") (class "Default")
      (node (ref "U1") (pin "97") (pinfunction "PF0_(ADC0)_97") (pintype "bidirectional"))
    )
    (net (code "81") (name "unconnected-(U1-PF1_(ADC1)-Pad96)") (class "Default")
      (node (ref "U1") (pin "96") (pinfunction "PF1_(ADC1)_96") (pintype "bidirectional"))
    )
    (net (code "82") (name "unconnected-(U1-PF2_(ADC2)-Pad95)") (class "Default")
      (node (ref "U1") (pin "95") (pinfunction "PF2_(ADC2)_95") (pintype "bidirectional"))
    )
    (net (code "83") (name "unconnected-(U1-PF3_(ADC3)-Pad94)") (class "Default")
      (node (ref "U1") (pin "94") (pinfunction "PF3_(ADC3)_94") (pintype "bidirectional"))
    )
    (net (code "84") (name "unconnected-(U1-PG0_(~WR)-Pad51)") (class "Default")
      (node (ref "U1") (pin "51") (pinfunction "PG0_(~WR)_51") (pintype "bidirectional"))
    )
    (net (code "85") (name "unconnected-(U1-PG1_(~RD)-Pad52)") (class "Default")
      (node (ref "U1") (pin "52") (pinfunction "PG1_(~RD)_52") (pintype "bidirectional"))
    )
    (net (code "86") (name "unconnected-(U1-PG2_(ALE)-Pad70)") (class "Default")
      (node (ref "U1") (pin "70") (pinfunction "PG2_(ALE)_70") (pintype "bidirectional"))
    )
    (net (code "87") (name "unconnected-(U1-PJ0_(RXD3{slash}PCINT9)-Pad63)") (class "Default")
      (node (ref "U1") (pin "63") (pinfunction "PJ0_(RXD3/PCINT9)_63") (pintype "bidirectional"))
    )
    (net (code "88") (name "unconnected-(U1-PJ1_(TXD3{slash}PCINT10)-Pad64)") (class "Default")
      (node (ref "U1") (pin "64") (pinfunction "PJ1_(TXD3/PCINT10)_64") (pintype "bidirectional"))
    )
    (net (code "89") (name "unconnected-(U1-PJ2_(XCK3{slash}PCINT11)-Pad65)") (class "Default")
      (node (ref "U1") (pin "65") (pinfunction "PJ2_(XCK3/PCINT11)_65") (pintype "bidirectional"))
    )
    (net (code "90") (name "unconnected-(U1-PJ3_(PCINT12)-Pad66)") (class "Default")
      (node (ref "U1") (pin "66") (pinfunction "PJ3_(PCINT12)_66") (pintype "bidirectional"))
    )
    (net (code "91") (name "unconnected-(U1-PJ4_(PCINT13)-Pad67)") (class "Default")
      (node (ref "U1") (pin "67") (pinfunction "PJ4_(PCINT13)_67") (pintype "bidirectional"))
    )
    (net (code "92") (name "unconnected-(U1-PJ5_(PCINT14)-Pad68)") (class "Default")
      (node (ref "U1") (pin "68") (pinfunction "PJ5_(PCINT14)_68") (pintype "bidirectional"))
    )
    (net (code "93") (name "unconnected-(U1-PJ6_(PCINT15)-Pad69)") (class "Default")
      (node (ref "U1") (pin "69") (pinfunction "PJ6_(PCINT15)_69") (pintype "bidirectional"))
    )
    (net (code "94") (name "unconnected-(U1-PJ7-Pad79)") (class "Default")
      (node (ref "U1") (pin "79") (pinfunction "PJ7_79") (pintype "bidirectional"))
    )
    (net (code "95") (name "unconnected-(U1-PK0_(ADC8{slash}PCINT16)-Pad89)") (class "Default")
      (node (ref "U1") (pin "89") (pinfunction "PK0_(ADC8/PCINT16)_89") (pintype "bidirectional"))
    )
    (net (code "96") (name "unconnected-(U1-PK1_(ADC9{slash}PCINT17)-Pad88)") (class "Default")
      (node (ref "U1") (pin "88") (pinfunction "PK1_(ADC9/PCINT17)_88") (pintype "bidirectional"))
    )
    (net (code "97") (name "unconnected-(U1-PK2_(ADC10{slash}PCINT18)-Pad87)") (class "Default")
      (node (ref "U1") (pin "87") (pinfunction "PK2_(ADC10/PCINT18)_87") (pintype "bidirectional"))
    )
    (net (code "98") (name "unconnected-(U1-PK3_(ADC11{slash}PCINT19)-Pad86)") (class "Default")
      (node (ref "U1") (pin "86") (pinfunction "PK3_(ADC11/PCINT19)_86") (pintype "bidirectional"))
    )
    (net (code "99") (name "unconnected-(U1-PK4_(ADC12{slash}PCINT20)-Pad85)") (class "Default")
      (node (ref "U1") (pin "85") (pinfunction "PK4_(ADC12/PCINT20)_85") (pintype "bidirectional"))
    )
    (net (code "100") (name "unconnected-(U1-PK5_(ADC13{slash}PCINT21)-Pad84)") (class "Default")
      (node (ref "U1") (pin "84") (pinfunction "PK5_(ADC13/PCINT21)_84") (pintype "bidirectional"))
    )
    (net (code "101") (name "unconnected-(U1-PK6_(ADC14{slash}PCINT22)-Pad83)") (class "Default")
      (node (ref "U1") (pin "83") (pinfunction "PK6_(ADC14/PCINT22)_83") (pintype "bidirectional"))
    )
    (net (code "102") (name "unconnected-(U1-PK7_(ADC15{slash}PCINT23)-Pad82)") (class "Default")
      (node (ref "U1") (pin "82") (pinfunction "PK7_(ADC15/PCINT23)_82") (pintype "bidirectional"))
    )
    (net (code "103") (name "unconnected-(U1-PL6-Pad41)") (class "Default")
      (node (ref "U1") (pin "41") (pinfunction "PL6_41") (pintype "bidirectional"))
    )
    (net (code "104") (name "unconnected-(U1-PL7-Pad42)") (class "Default")
      (node (ref "U1") (pin "42") (pinfunction "PL7_42") (pintype "bidirectional"))
    )
    (net (code "105") (name "unconnected-(U2-SPLIT-Pad5)") (class "Default")
      (node (ref "U2") (pin "5") (pinfunction "SPLIT_5") (pintype "passive+no_connect"))
    )
    (net (code "106") (name "unconnected-(U3-CLKOUT{slash}SOF-Pad3)") (class "Default")
      (node (ref "U3") (pin "3") (pinfunction "CLKOUT/SOF_3") (pintype "passive"))
    )
    (net (code "107") (name "unconnected-(U3-NC-Pad6)") (class "Default")
      (node (ref "U3") (pin "6") (pinfunction "NC_6") (pintype "passive+no_connect"))
    )
    (net (code "108") (name "unconnected-(U3-NC-Pad15)") (class "Default")
      (node (ref "U3") (pin "15") (pinfunction "NC_15") (pintype "passive+no_connect"))
    )
    (net (code "109") (name "unconnected-(U3-RX0BF#-Pad12)") (class "Default")
      (node (ref "U3") (pin "12") (pinfunction "RX0BF#_12") (pintype "passive"))
    )
    (net (code "110") (name "unconnected-(U3-RX1BF#-Pad11)") (class "Default")
      (node (ref "U3") (pin "11") (pinfunction "RX1BF#_11") (pintype "passive"))
    )
    (net (code "111") (name "unconnected-(U3-TX0RTS#-Pad4)") (class "Default")
      (node (ref "U3") (pin "4") (pinfunction "TX0RTS#_4") (pintype "passive"))
    )
    (net (code "112") (name "unconnected-(U3-TX1RTS#-Pad5)") (class "Default")
      (node (ref "U3") (pin "5") (pinfunction "TX1RTS#_5") (pintype "passive"))
    )
    (net (code "113") (name "unconnected-(U3-TX2RTS#-Pad7)") (class "Default")
      (node (ref "U3") (pin "7") (pinfunction "TX2RTS#_7") (pintype "passive"))
    )
  )
)
